# SOCPSBanks.net
KiCad netlist of a schematic drawn in Altium Designer
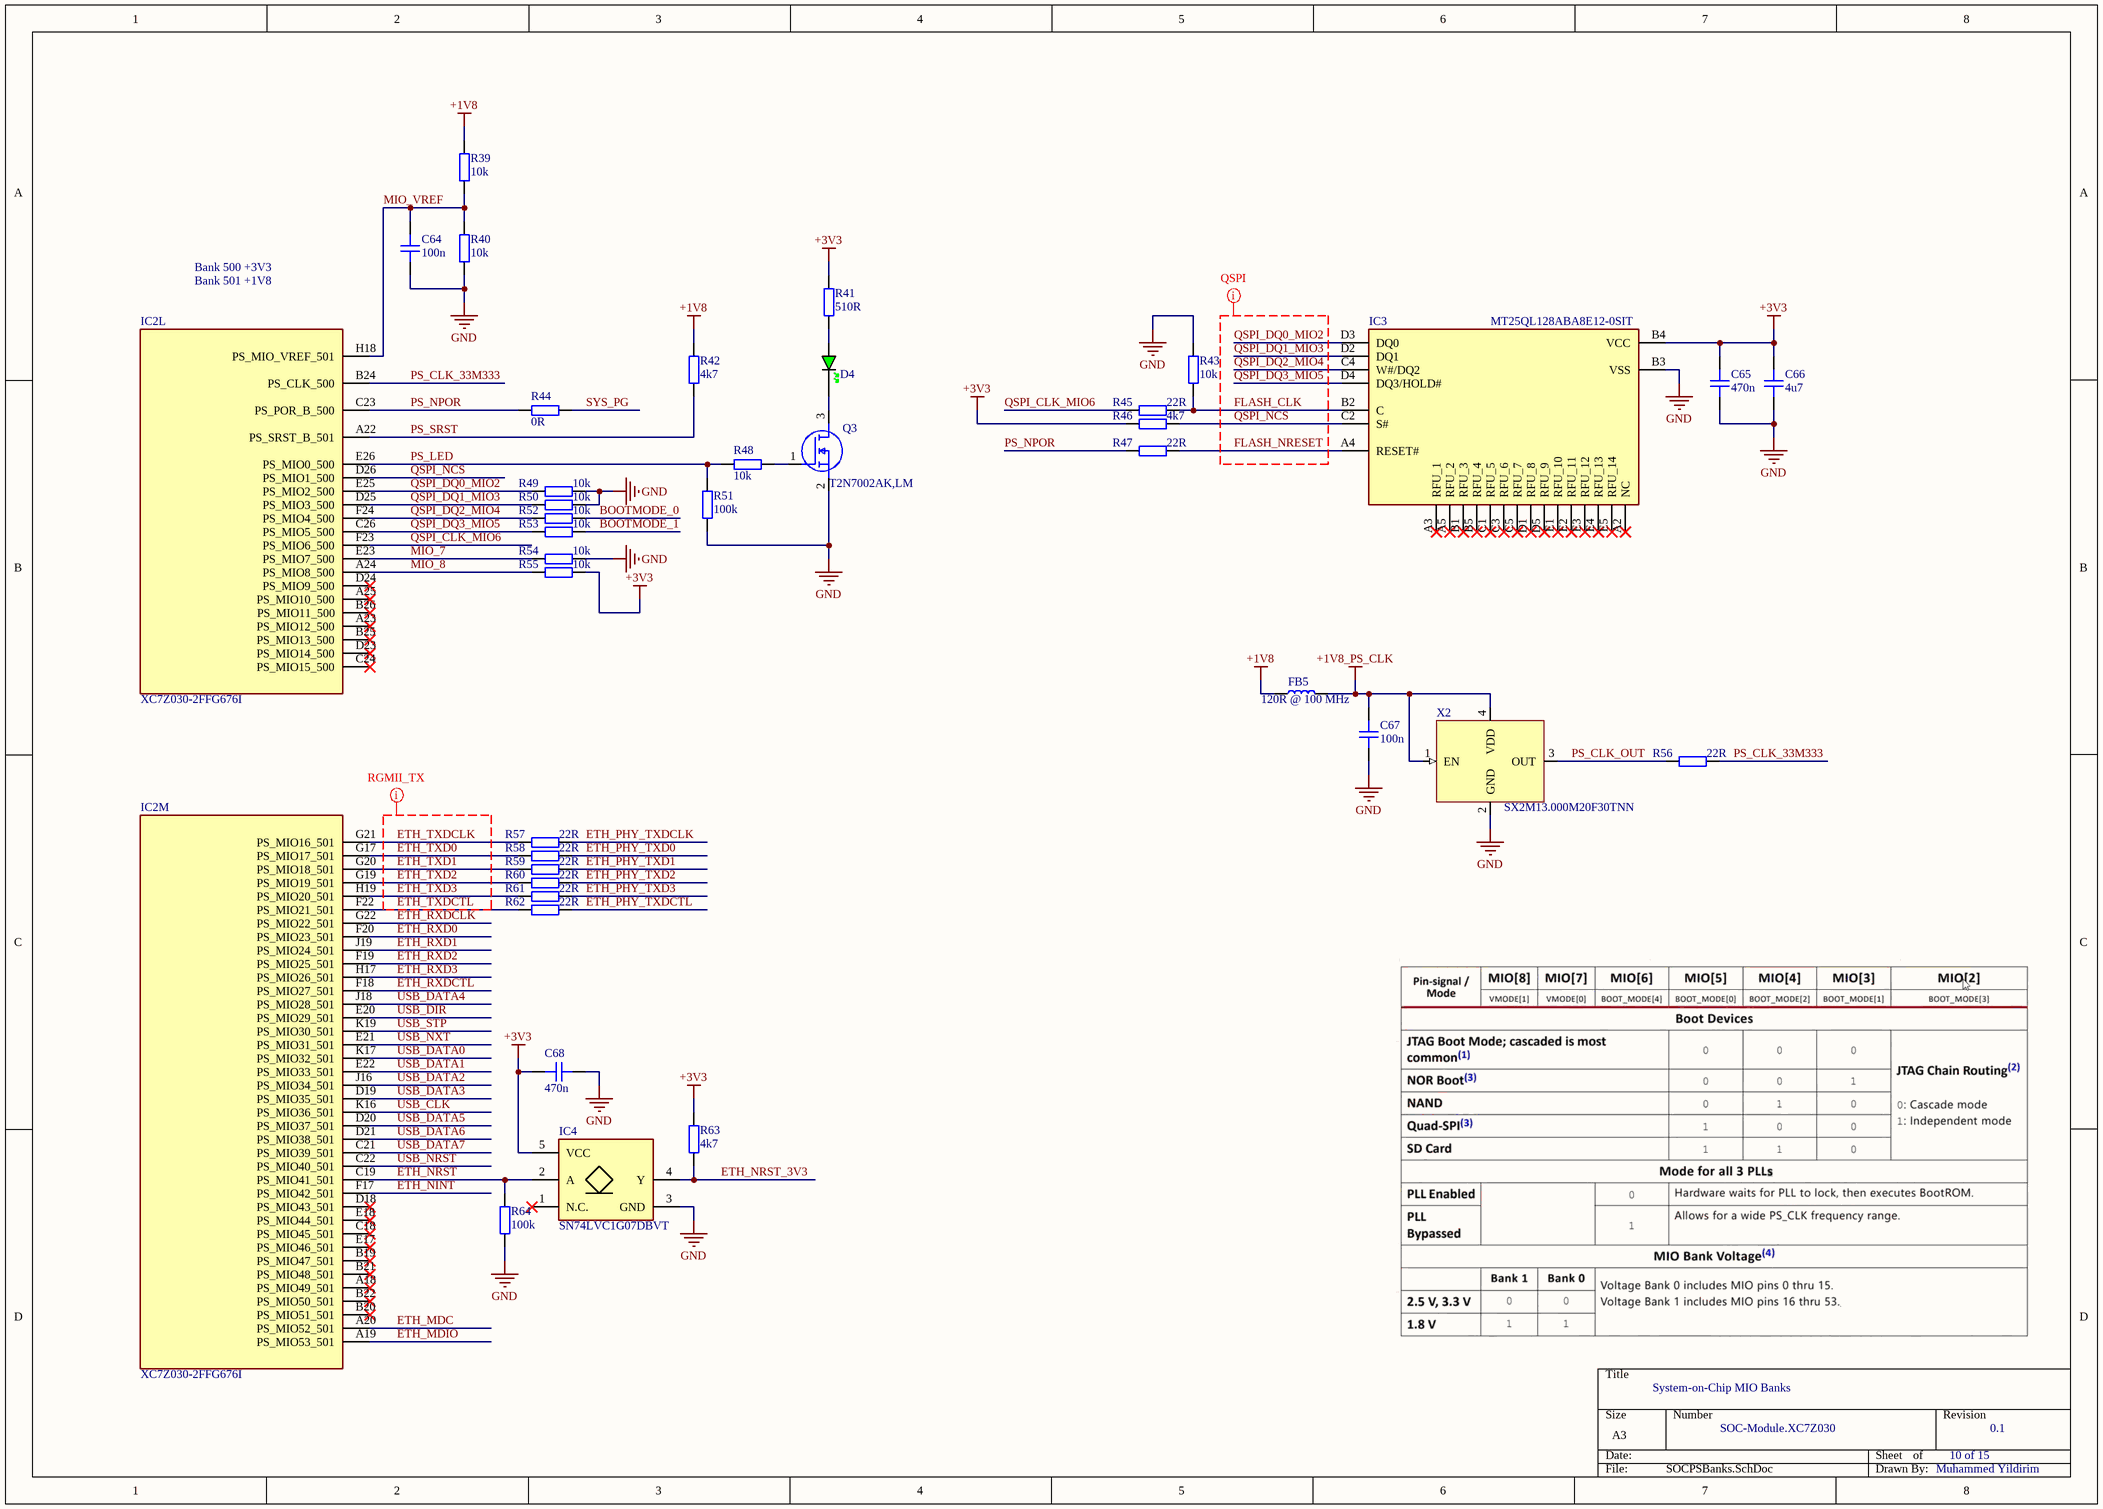
[diagram p0: SOCPSBanks.SchDoc]

(export (version "E")
  (design (tool "Eeschema 10.0.6"))
  (components
    (comp (ref "C64")
      (value "100n")
      (footprint "CAP_0201")
      (description "Capacitor SMD 0201")
      (libsource (lib "Schematic-Lib-PhilsLab") (part "CAP_0201"))
    )
    (comp (ref "C65")
      (value "470n")
      (footprint "CAP_0201")
      (description "Capacitor SMD 0201")
      (libsource (lib "Schematic-Lib-PhilsLab") (part "CAP_0201"))
    )
    (comp (ref "C66")
      (value "4u7")
      (footprint "CAP_0402")
      (description "Capacitor SMD 0402")
      (libsource (lib "Schematic-Lib-PhilsLab") (part "CAP_0402"))
    )
    (comp (ref "C67")
      (value "100n")
      (footprint "CAP_0201")
      (description "Capacitor SMD 0201")
      (libsource (lib "Schematic-Lib-PhilsLab") (part "CAP_0201"))
    )
    (comp (ref "C68")
      (value "470n")
      (footprint "CAP_0201")
      (description "Capacitor SMD 0201")
      (libsource (lib "Schematic-Lib-PhilsLab") (part "CAP_0201"))
    )
    (comp (ref "D4")
      (value "GREEN")
      (footprint "LED_0603_GREEN")
      (description "LED 0603 GREEN SMD")
      (libsource (lib "Schematic-Lib-PhilsLab") (part "LED_0603_GREEN"))
    )
    (comp (ref "FB5")
      (value "120R @ 100 MHz")
      (footprint "Footprint-Lib-PhilsLab:IND_0201")
      (description "Inductor SMD 0201")
      (fields
        (field (name "MANUFACTURER_PART_NUMBER") "LQP03HQ56NH02D")
        (field (name "MOUSER PART NUMBER") "81-LQP03HQ56NH02D")
      )
      (libsource (lib "Schematic-Lib-PhilsLab") (part "IND_0201"))
    )
    (comp (ref "IC2")
      (value "XC7Z030-2FFG676I")
      (footprint "XC7Z030PCBLib:BGA676C100P26X26_2700X2700X324")
      (description "Integrated Circuit")
      (fields (field (name "MOUSER PART NUMBER") "217-XC7Z030-2FFG676I"))
      (libsource (lib "XC7Z030SCHLib") (part "XC7Z030-2FFG676I"))
    )
    (comp (ref "IC3")
      (value "MT25QL128ABA8E12-0SIT")
      (footprint "XC7Z030PCBLib:BGA24C100P5X5_600X800X120")
      (description "Micron 128 Mb QSPI NOR-Flash")
      (fields (field (name "MOUSER PART NUMBER") "340-283174-TRAY"))
      (libsource (lib "XC7Z030SCHLib") (part "MT25QL128ABA8E12-0SIT"))
    )
    (comp (ref "IC4")
      (value "SN74LVC1G07DBVT")
      (footprint "XC7Z030PCBLib:SOT95P280X145-5N")
      (description "Integrated Circuit")
      (fields (field (name "MOUSER PART NUMBER") "595-SN74LVC1G07DBVT"))
      (libsource (lib "XC7Z030SCHLib") (part "SN74LVC1G07DBVT"))
    )
    (comp (ref "Q3")
      (value "T2N7002AK,LM")
      (footprint "Footprint-Lib-PhilsLab:TBAT54CLM")
      (description "MOSFET (N-Channel)")
      (fields (field (name "MOUSER PART NUMBER") "757-T2N7002AKLM"))
      (libsource (lib "Schematic-Lib-PhilsLab") (part "T2N7002AK,LM"))
    )
    (comp (ref "R39")
      (value "10k")
      (footprint "RES_0201")
      (description "Resistor SMD 0201")
      (libsource (lib "Schematic-Lib-PhilsLab") (part "RES_0201"))
    )
    (comp (ref "R40")
      (value "10k")
      (footprint "RES_0201")
      (description "Resistor SMD 0201")
      (libsource (lib "Schematic-Lib-PhilsLab") (part "RES_0201"))
    )
    (comp (ref "R41")
      (value "510R")
      (footprint "RES_0603")
      (description "Resistor SMD 0603")
      (libsource (lib "Schematic-Lib-PhilsLab") (part "RES_0603"))
    )
    (comp (ref "R42")
      (value "4k7")
      (footprint "RES_0201")
      (description "Resistor SMD 0201")
      (libsource (lib "Schematic-Lib-PhilsLab") (part "RES_0201"))
    )
    (comp (ref "R43")
      (value "10k")
      (footprint "RES_0201")
      (description "Resistor SMD 0201")
      (libsource (lib "Schematic-Lib-PhilsLab") (part "RES_0201"))
    )
    (comp (ref "R44")
      (value "0R")
      (footprint "RES_0402")
      (description "Resistor SMD 0402")
      (libsource (lib "Schematic-Lib-PhilsLab") (part "RES_0402"))
    )
    (comp (ref "R45")
      (value "22R")
      (footprint "RES_0201")
      (description "Resistor SMD 0201")
      (libsource (lib "Schematic-Lib-PhilsLab") (part "RES_0201"))
    )
    (comp (ref "R46")
      (value "4k7")
      (footprint "RES_0201")
      (description "Resistor SMD 0201")
      (libsource (lib "Schematic-Lib-PhilsLab") (part "RES_0201"))
    )
    (comp (ref "R47")
      (value "22R")
      (footprint "RES_0201")
      (description "Resistor SMD 0201")
      (libsource (lib "Schematic-Lib-PhilsLab") (part "RES_0201"))
    )
    (comp (ref "R48")
      (value "10k")
      (footprint "RES_0201")
      (description "Resistor SMD 0201")
      (libsource (lib "Schematic-Lib-PhilsLab") (part "RES_0201"))
    )
    (comp (ref "R49")
      (value "10k")
      (footprint "RES_0201")
      (description "Resistor SMD 0201")
      (libsource (lib "Schematic-Lib-PhilsLab") (part "RES_0201"))
    )
    (comp (ref "R50")
      (value "10k")
      (footprint "RES_0201")
      (description "Resistor SMD 0201")
      (libsource (lib "Schematic-Lib-PhilsLab") (part "RES_0201"))
    )
    (comp (ref "R51")
      (value "100k")
      (footprint "RES_0201")
      (description "Resistor SMD 0201")
      (libsource (lib "Schematic-Lib-PhilsLab") (part "RES_0201"))
    )
    (comp (ref "R52")
      (value "10k")
      (footprint "RES_0201")
      (description "Resistor SMD 0201")
      (libsource (lib "Schematic-Lib-PhilsLab") (part "RES_0201"))
    )
    (comp (ref "R53")
      (value "10k")
      (footprint "RES_0201")
      (description "Resistor SMD 0201")
      (libsource (lib "Schematic-Lib-PhilsLab") (part "RES_0201"))
    )
    (comp (ref "R54")
      (value "10k")
      (footprint "RES_0201")
      (description "Resistor SMD 0201")
      (libsource (lib "Schematic-Lib-PhilsLab") (part "RES_0201"))
    )
    (comp (ref "R55")
      (value "10k")
      (footprint "RES_0201")
      (description "Resistor SMD 0201")
      (libsource (lib "Schematic-Lib-PhilsLab") (part "RES_0201"))
    )
    (comp (ref "R56")
      (value "22R")
      (footprint "RES_0201")
      (description "Resistor SMD 0201")
      (libsource (lib "Schematic-Lib-PhilsLab") (part "RES_0201"))
    )
    (comp (ref "R57")
      (value "22R")
      (footprint "RES_0201")
      (description "Resistor SMD 0201")
      (libsource (lib "Schematic-Lib-PhilsLab") (part "RES_0201"))
    )
    (comp (ref "R58")
      (value "22R")
      (footprint "RES_0201")
      (description "Resistor SMD 0201")
      (libsource (lib "Schematic-Lib-PhilsLab") (part "RES_0201"))
    )
    (comp (ref "R59")
      (value "22R")
      (footprint "RES_0201")
      (description "Resistor SMD 0201")
      (libsource (lib "Schematic-Lib-PhilsLab") (part "RES_0201"))
    )
    (comp (ref "R60")
      (value "22R")
      (footprint "RES_0201")
      (description "Resistor SMD 0201")
      (libsource (lib "Schematic-Lib-PhilsLab") (part "RES_0201"))
    )
    (comp (ref "R61")
      (value "22R")
      (footprint "RES_0201")
      (description "Resistor SMD 0201")
      (libsource (lib "Schematic-Lib-PhilsLab") (part "RES_0201"))
    )
    (comp (ref "R62")
      (value "22R")
      (footprint "RES_0201")
      (description "Resistor SMD 0201")
      (libsource (lib "Schematic-Lib-PhilsLab") (part "RES_0201"))
    )
    (comp (ref "R63")
      (value "4k7")
      (footprint "RES_0201")
      (description "Resistor SMD 0201")
      (libsource (lib "Schematic-Lib-PhilsLab") (part "RES_0201"))
    )
    (comp (ref "R64")
      (value "100k")
      (footprint "RES_0201")
      (description "Resistor SMD 0201")
      (libsource (lib "Schematic-Lib-PhilsLab") (part "RES_0201"))
    )
    (comp (ref "X2")
      (value "SX2M13.000M20F30TNN")
      (footprint "XTAL_2520")
      (fields
        (field (name "MANUFACTURER") "ECS")
        (field (name "MANUFACTURER PART NUMBER") "ECS-2520MV-130-BN-TR")
      )
      (libsource (lib "Schematic-Lib-PhilsLab") (part "ECS-2520MV-130-BN-TR"))
    )
  )
  (nets
    (net (code "1") (name "+1V8") (class "Default")
      (node (ref "FB5") (pin "1") (pinfunction "1_1") (pintype "passive"))
      (node (ref "R39") (pin "1") (pinfunction "1_1") (pintype "passive"))
      (node (ref "R42") (pin "2") (pinfunction "2_2") (pintype "passive"))
    )
    (net (code "2") (name "+1V8_PS_CLK") (class "Default")
      (node (ref "C67") (pin "1") (pinfunction "1_1") (pintype "passive"))
      (node (ref "FB5") (pin "2") (pinfunction "2_2") (pintype "passive"))
      (node (ref "X2") (pin "1") (pinfunction "EN_1") (pintype "input"))
      (node (ref "X2") (pin "4") (pinfunction "VDD_4") (pintype "power_in"))
    )
    (net (code "3") (name "+3V3") (class "Default")
      (node (ref "C65") (pin "2") (pinfunction "2_2") (pintype "passive"))
      (node (ref "C66") (pin "2") (pinfunction "2_2") (pintype "passive"))
      (node (ref "C68") (pin "2") (pinfunction "2_2") (pintype "passive"))
      (node (ref "IC3") (pin "B4") (pinfunction "VCC_B4") (pintype "passive"))
      (node (ref "IC4") (pin "5") (pinfunction "VCC_5") (pintype "passive"))
      (node (ref "R41") (pin "2") (pinfunction "2_2") (pintype "passive"))
      (node (ref "R46") (pin "2") (pinfunction "2_2") (pintype "passive"))
      (node (ref "R55") (pin "1") (pinfunction "1_1") (pintype "passive"))
      (node (ref "R63") (pin "2") (pinfunction "2_2") (pintype "passive"))
    )
    (net (code "4") (name "/BOOTMODE_0") (class "Default")
      (node (ref "R52") (pin "1") (pinfunction "1_1") (pintype "passive"))
    )
    (net (code "5") (name "/BOOTMODE_1") (class "Default")
      (node (ref "R53") (pin "1") (pinfunction "1_1") (pintype "passive"))
    )
    (net (code "6") (name "/ETH_MDC") (class "Default")
      (node (ref "IC2") (pin "A20") (pinfunction "PS_MIO52_501_A20") (pintype "passive"))
    )
    (net (code "7") (name "/ETH_MDIO") (class "Default")
      (node (ref "IC2") (pin "A19") (pinfunction "PS_MIO53_501_A19") (pintype "passive"))
    )
    (net (code "8") (name "/ETH_NINT") (class "Default")
      (node (ref "IC2") (pin "F17") (pinfunction "PS_MIO42_501_F17") (pintype "passive"))
    )
    (net (code "9") (name "/ETH_NRST") (class "Default")
      (node (ref "IC2") (pin "C19") (pinfunction "PS_MIO41_501_C19") (pintype "passive"))
      (node (ref "IC4") (pin "2") (pinfunction "A_2") (pintype "passive"))
      (node (ref "R64") (pin "2") (pinfunction "2_2") (pintype "passive"))
    )
    (net (code "10") (name "/ETH_NRST_3V3") (class "Default")
      (node (ref "IC4") (pin "4") (pinfunction "Y_4") (pintype "passive"))
      (node (ref "R63") (pin "1") (pinfunction "1_1") (pintype "passive"))
    )
    (net (code "11") (name "/ETH_PHY_TXD0") (class "Default")
      (node (ref "R58") (pin "1") (pinfunction "1_1") (pintype "passive"))
    )
    (net (code "12") (name "/ETH_PHY_TXD1") (class "Default")
      (node (ref "R59") (pin "1") (pinfunction "1_1") (pintype "passive"))
    )
    (net (code "13") (name "/ETH_PHY_TXD2") (class "Default")
      (node (ref "R60") (pin "1") (pinfunction "1_1") (pintype "passive"))
    )
    (net (code "14") (name "/ETH_PHY_TXD3") (class "Default")
      (node (ref "R61") (pin "1") (pinfunction "1_1") (pintype "passive"))
    )
    (net (code "15") (name "/ETH_PHY_TXDCLK") (class "Default")
      (node (ref "R57") (pin "1") (pinfunction "1_1") (pintype "passive"))
    )
    (net (code "16") (name "/ETH_PHY_TXDCTL") (class "Default")
      (node (ref "R62") (pin "1") (pinfunction "1_1") (pintype "passive"))
    )
    (net (code "17") (name "/ETH_RXD0") (class "Default")
      (node (ref "IC2") (pin "F20") (pinfunction "PS_MIO23_501_F20") (pintype "passive"))
    )
    (net (code "18") (name "/ETH_RXD1") (class "Default")
      (node (ref "IC2") (pin "J19") (pinfunction "PS_MIO24_501_J19") (pintype "passive"))
    )
    (net (code "19") (name "/ETH_RXD2") (class "Default")
      (node (ref "IC2") (pin "F19") (pinfunction "PS_MIO25_501_F19") (pintype "passive"))
    )
    (net (code "20") (name "/ETH_RXD3") (class "Default")
      (node (ref "IC2") (pin "H17") (pinfunction "PS_MIO26_501_H17") (pintype "passive"))
    )
    (net (code "21") (name "/ETH_RXDCLK") (class "Default")
      (node (ref "IC2") (pin "G22") (pinfunction "PS_MIO22_501_G22") (pintype "passive"))
    )
    (net (code "22") (name "/ETH_RXDCTL") (class "Default")
      (node (ref "IC2") (pin "F18") (pinfunction "PS_MIO27_501_F18") (pintype "passive"))
    )
    (net (code "23") (name "/ETH_TXD0") (class "Default")
      (node (ref "IC2") (pin "G17") (pinfunction "PS_MIO17_501_G17") (pintype "passive"))
      (node (ref "R58") (pin "2") (pinfunction "2_2") (pintype "passive"))
    )
    (net (code "24") (name "/ETH_TXD1") (class "Default")
      (node (ref "IC2") (pin "G20") (pinfunction "PS_MIO18_501_G20") (pintype "passive"))
      (node (ref "R59") (pin "2") (pinfunction "2_2") (pintype "passive"))
    )
    (net (code "25") (name "/ETH_TXD2") (class "Default")
      (node (ref "IC2") (pin "G19") (pinfunction "PS_MIO19_501_G19") (pintype "passive"))
      (node (ref "R60") (pin "2") (pinfunction "2_2") (pintype "passive"))
    )
    (net (code "26") (name "/ETH_TXD3") (class "Default")
      (node (ref "IC2") (pin "H19") (pinfunction "PS_MIO20_501_H19") (pintype "passive"))
      (node (ref "R61") (pin "2") (pinfunction "2_2") (pintype "passive"))
    )
    (net (code "27") (name "/ETH_TXDCLK") (class "Default")
      (node (ref "IC2") (pin "G21") (pinfunction "PS_MIO16_501_G21") (pintype "passive"))
      (node (ref "R57") (pin "2") (pinfunction "2_2") (pintype "passive"))
    )
    (net (code "28") (name "/ETH_TXDCTL") (class "Default")
      (node (ref "IC2") (pin "F22") (pinfunction "PS_MIO21_501_F22") (pintype "passive"))
      (node (ref "R62") (pin "2") (pinfunction "2_2") (pintype "passive"))
    )
    (net (code "29") (name "/FLASH_CLK") (class "Default")
      (node (ref "IC3") (pin "B2") (pinfunction "C_B2") (pintype "passive"))
      (node (ref "R43") (pin "2") (pinfunction "2_2") (pintype "passive"))
      (node (ref "R45") (pin "1") (pinfunction "1_1") (pintype "passive"))
    )
    (net (code "30") (name "/FLASH_NRESET") (class "Default")
      (node (ref "IC3") (pin "A4") (pinfunction "RESET#_A4") (pintype "passive"))
      (node (ref "R47") (pin "1") (pinfunction "1_1") (pintype "passive"))
    )
    (net (code "31") (name "/MIO_7") (class "Default")
      (node (ref "IC2") (pin "E23") (pinfunction "PS_MIO7_500_E23") (pintype "passive"))
      (node (ref "R54") (pin "2") (pinfunction "2_2") (pintype "passive"))
    )
    (net (code "32") (name "/MIO_8") (class "Default")
      (node (ref "IC2") (pin "A24") (pinfunction "PS_MIO8_500_A24") (pintype "passive"))
      (node (ref "R55") (pin "2") (pinfunction "2_2") (pintype "passive"))
    )
    (net (code "33") (name "/MIO_VREF") (class "Default")
      (node (ref "C64") (pin "1") (pinfunction "1_1") (pintype "passive"))
      (node (ref "IC2") (pin "H18") (pinfunction "PS_MIO_VREF_501_H18") (pintype "passive"))
      (node (ref "R39") (pin "2") (pinfunction "2_2") (pintype "passive"))
      (node (ref "R40") (pin "1") (pinfunction "1_1") (pintype "passive"))
    )
    (net (code "34") (name "/PS_CLK_33M333") (class "Default")
      (node (ref "IC2") (pin "B24") (pinfunction "PS_CLK_500_B24") (pintype "passive"))
      (node (ref "R56") (pin "2") (pinfunction "2_2") (pintype "passive"))
    )
    (net (code "35") (name "/PS_CLK_OUT") (class "Default")
      (node (ref "R56") (pin "1") (pinfunction "1_1") (pintype "passive"))
      (node (ref "X2") (pin "3") (pinfunction "OUT_3") (pintype "passive"))
    )
    (net (code "36") (name "/PS_LED") (class "Default")
      (node (ref "IC2") (pin "E26") (pinfunction "PS_MIO0_500_E26") (pintype "passive"))
      (node (ref "R48") (pin "2") (pinfunction "2_2") (pintype "passive"))
      (node (ref "R51") (pin "2") (pinfunction "2_2") (pintype "passive"))
    )
    (net (code "37") (name "/PS_NPOR") (class "Default")
      (node (ref "IC2") (pin "C23") (pinfunction "PS_POR_B_500_C23") (pintype "passive"))
      (node (ref "R44") (pin "2") (pinfunction "2_2") (pintype "passive"))
      (node (ref "R47") (pin "2") (pinfunction "2_2") (pintype "passive"))
    )
    (net (code "38") (name "/PS_SRST") (class "Default")
      (node (ref "IC2") (pin "A22") (pinfunction "PS_SRST_B_501_A22") (pintype "passive"))
      (node (ref "R42") (pin "1") (pinfunction "1_1") (pintype "passive"))
    )
    (net (code "39") (name "/QSPI_CLK_MIO6") (class "Default")
      (node (ref "IC2") (pin "F23") (pinfunction "PS_MIO6_500_F23") (pintype "passive"))
      (node (ref "R45") (pin "2") (pinfunction "2_2") (pintype "passive"))
    )
    (net (code "40") (name "/QSPI_DQ0_MIO2") (class "Default")
      (node (ref "IC2") (pin "E25") (pinfunction "PS_MIO2_500_E25") (pintype "passive"))
      (node (ref "IC3") (pin "D3") (pinfunction "DQ0_D3") (pintype "passive"))
      (node (ref "R49") (pin "2") (pinfunction "2_2") (pintype "passive"))
    )
    (net (code "41") (name "/QSPI_DQ1_MIO3") (class "Default")
      (node (ref "IC2") (pin "D25") (pinfunction "PS_MIO3_500_D25") (pintype "passive"))
      (node (ref "IC3") (pin "D2") (pinfunction "DQ1_D2") (pintype "passive"))
      (node (ref "R50") (pin "2") (pinfunction "2_2") (pintype "passive"))
    )
    (net (code "42") (name "/QSPI_DQ2_MIO4") (class "Default")
      (node (ref "IC2") (pin "F24") (pinfunction "PS_MIO4_500_F24") (pintype "passive"))
      (node (ref "IC3") (pin "C4") (pinfunction "W#/DQ2_C4") (pintype "passive"))
      (node (ref "R52") (pin "2") (pinfunction "2_2") (pintype "passive"))
    )
    (net (code "43") (name "/QSPI_DQ3_MIO5") (class "Default")
      (node (ref "IC2") (pin "C26") (pinfunction "PS_MIO5_500_C26") (pintype "passive"))
      (node (ref "IC3") (pin "D4") (pinfunction "DQ3/HOLD#_D4") (pintype "passive"))
      (node (ref "R53") (pin "2") (pinfunction "2_2") (pintype "passive"))
    )
    (net (code "44") (name "/QSPI_NCS") (class "Default")
      (node (ref "IC2") (pin "D26") (pinfunction "PS_MIO1_500_D26") (pintype "passive"))
      (node (ref "IC3") (pin "C2") (pinfunction "S#_C2") (pintype "passive"))
      (node (ref "R46") (pin "1") (pinfunction "1_1") (pintype "passive"))
    )
    (net (code "45") (name "/SYS_PG") (class "Default")
      (node (ref "R44") (pin "1") (pinfunction "1_1") (pintype "passive"))
    )
    (net (code "46") (name "/USB_CLK") (class "Default")
      (node (ref "IC2") (pin "K16") (pinfunction "PS_MIO36_501_K16") (pintype "passive"))
    )
    (net (code "47") (name "/USB_DATA0") (class "Default")
      (node (ref "IC2") (pin "K17") (pinfunction "PS_MIO32_501_K17") (pintype "passive"))
    )
    (net (code "48") (name "/USB_DATA1") (class "Default")
      (node (ref "IC2") (pin "E22") (pinfunction "PS_MIO33_501_E22") (pintype "passive"))
    )
    (net (code "49") (name "/USB_DATA2") (class "Default")
      (node (ref "IC2") (pin "J16") (pinfunction "PS_MIO34_501_J16") (pintype "passive"))
    )
    (net (code "50") (name "/USB_DATA3") (class "Default")
      (node (ref "IC2") (pin "D19") (pinfunction "PS_MIO35_501_D19") (pintype "passive"))
    )
    (net (code "51") (name "/USB_DATA4") (class "Default")
      (node (ref "IC2") (pin "J18") (pinfunction "PS_MIO28_501_J18") (pintype "passive"))
    )
    (net (code "52") (name "/USB_DATA5") (class "Default")
      (node (ref "IC2") (pin "D20") (pinfunction "PS_MIO37_501_D20") (pintype "passive"))
    )
    (net (code "53") (name "/USB_DATA6") (class "Default")
      (node (ref "IC2") (pin "D21") (pinfunction "PS_MIO38_501_D21") (pintype "passive"))
    )
    (net (code "54") (name "/USB_DATA7") (class "Default")
      (node (ref "IC2") (pin "C21") (pinfunction "PS_MIO39_501_C21") (pintype "passive"))
    )
    (net (code "55") (name "/USB_DIR") (class "Default")
      (node (ref "IC2") (pin "E20") (pinfunction "PS_MIO29_501_E20") (pintype "passive"))
    )
    (net (code "56") (name "/USB_NRST") (class "Default")
      (node (ref "IC2") (pin "C22") (pinfunction "PS_MIO40_501_C22") (pintype "passive"))
    )
    (net (code "57") (name "/USB_NXT") (class "Default")
      (node (ref "IC2") (pin "E21") (pinfunction "PS_MIO31_501_E21") (pintype "passive"))
    )
    (net (code "58") (name "/USB_STP") (class "Default")
      (node (ref "IC2") (pin "K19") (pinfunction "PS_MIO30_501_K19") (pintype "passive"))
    )
    (net (code "59") (name "GND") (class "Default")
      (node (ref "C64") (pin "2") (pinfunction "2_2") (pintype "passive"))
      (node (ref "C65") (pin "1") (pinfunction "1_1") (pintype "passive"))
      (node (ref "C66") (pin "1") (pinfunction "1_1") (pintype "passive"))
      (node (ref "C67") (pin "2") (pinfunction "2_2") (pintype "passive"))
      (node (ref "C68") (pin "1") (pinfunction "1_1") (pintype "passive"))
      (node (ref "IC3") (pin "B3") (pinfunction "VSS_B3") (pintype "passive"))
      (node (ref "IC4") (pin "3") (pinfunction "GND_3") (pintype "passive"))
      (node (ref "Q3") (pin "2") (pinfunction "S_2") (pintype "passive"))
      (node (ref "R40") (pin "2") (pinfunction "2_2") (pintype "passive"))
      (node (ref "R43") (pin "1") (pinfunction "1_1") (pintype "passive"))
      (node (ref "R49") (pin "1") (pinfunction "1_1") (pintype "passive"))
      (node (ref "R50") (pin "1") (pinfunction "1_1") (pintype "passive"))
      (node (ref "R51") (pin "1") (pinfunction "1_1") (pintype "passive"))
      (node (ref "R54") (pin "1") (pinfunction "1_1") (pintype "passive"))
      (node (ref "R64") (pin "1") (pinfunction "1_1") (pintype "passive"))
      (node (ref "X2") (pin "2") (pinfunction "GND_2") (pintype "power_in"))
    )
    (net (code "60") (name "Net-(D4-PadA)") (class "Default")
      (node (ref "D4") (pin "A") (pinfunction "A_A") (pintype "passive"))
      (node (ref "R41") (pin "1") (pinfunction "1_1") (pintype "passive"))
    )
    (net (code "61") (name "Net-(Q3-D)") (class "Default")
      (node (ref "D4") (pin "K") (pinfunction "K_K") (pintype "passive"))
      (node (ref "Q3") (pin "3") (pinfunction "D_3") (pintype "passive"))
    )
    (net (code "62") (name "Net-(Q3-G)") (class "Default")
      (node (ref "Q3") (pin "1") (pinfunction "G_1") (pintype "passive"))
      (node (ref "R48") (pin "1") (pinfunction "1_1") (pintype "passive"))
    )
    (net (code "63") (name "unconnected-(IC2L-PS_MIO9_500-PadD24)") (class "Default")
      (node (ref "IC2") (pin "D24") (pinfunction "PS_MIO9_500_D24") (pintype "passive+no_connect"))
    )
    (net (code "64") (name "unconnected-(IC2L-PS_MIO10_500-PadA25)") (class "Default")
      (node (ref "IC2") (pin "A25") (pinfunction "PS_MIO10_500_A25") (pintype "passive+no_connect"))
    )
    (net (code "65") (name "unconnected-(IC2L-PS_MIO11_500-PadB26)") (class "Default")
      (node (ref "IC2") (pin "B26") (pinfunction "PS_MIO11_500_B26") (pintype "passive+no_connect"))
    )
    (net (code "66") (name "unconnected-(IC2L-PS_MIO12_500-PadA23)") (class "Default")
      (node (ref "IC2") (pin "A23") (pinfunction "PS_MIO12_500_A23") (pintype "passive+no_connect"))
    )
    (net (code "67") (name "unconnected-(IC2L-PS_MIO13_500-PadB25)") (class "Default")
      (node (ref "IC2") (pin "B25") (pinfunction "PS_MIO13_500_B25") (pintype "passive+no_connect"))
    )
    (net (code "68") (name "unconnected-(IC2L-PS_MIO14_500-PadD23)") (class "Default")
      (node (ref "IC2") (pin "D23") (pinfunction "PS_MIO14_500_D23") (pintype "passive+no_connect"))
    )
    (net (code "69") (name "unconnected-(IC2L-PS_MIO15_500-PadC24)") (class "Default")
      (node (ref "IC2") (pin "C24") (pinfunction "PS_MIO15_500_C24") (pintype "passive+no_connect"))
    )
    (net (code "70") (name "unconnected-(IC2M-PS_MIO43_501-PadD18)") (class "Default")
      (node (ref "IC2") (pin "D18") (pinfunction "PS_MIO43_501_D18") (pintype "passive+no_connect"))
    )
    (net (code "71") (name "unconnected-(IC2M-PS_MIO44_501-PadE18)") (class "Default")
      (node (ref "IC2") (pin "E18") (pinfunction "PS_MIO44_501_E18") (pintype "passive+no_connect"))
    )
    (net (code "72") (name "unconnected-(IC2M-PS_MIO45_501-PadC18)") (class "Default")
      (node (ref "IC2") (pin "C18") (pinfunction "PS_MIO45_501_C18") (pintype "passive+no_connect"))
    )
    (net (code "73") (name "unconnected-(IC2M-PS_MIO46_501-PadE17)") (class "Default")
      (node (ref "IC2") (pin "E17") (pinfunction "PS_MIO46_501_E17") (pintype "passive+no_connect"))
    )
    (net (code "74") (name "unconnected-(IC2M-PS_MIO47_501-PadB19)") (class "Default")
      (node (ref "IC2") (pin "B19") (pinfunction "PS_MIO47_501_B19") (pintype "passive+no_connect"))
    )
    (net (code "75") (name "unconnected-(IC2M-PS_MIO48_501-PadB21)") (class "Default")
      (node (ref "IC2") (pin "B21") (pinfunction "PS_MIO48_501_B21") (pintype "passive+no_connect"))
    )
    (net (code "76") (name "unconnected-(IC2M-PS_MIO49_501-PadA18)") (class "Default")
      (node (ref "IC2") (pin "A18") (pinfunction "PS_MIO49_501_A18") (pintype "passive+no_connect"))
    )
    (net (code "77") (name "unconnected-(IC2M-PS_MIO50_501-PadB22)") (class "Default")
      (node (ref "IC2") (pin "B22") (pinfunction "PS_MIO50_501_B22") (pintype "passive+no_connect"))
    )
    (net (code "78") (name "unconnected-(IC2M-PS_MIO51_501-PadB20)") (class "Default")
      (node (ref "IC2") (pin "B20") (pinfunction "PS_MIO51_501_B20") (pintype "passive+no_connect"))
    )
    (net (code "79") (name "unconnected-(IC3-NC-PadA2)") (class "Default")
      (node (ref "IC3") (pin "A2") (pinfunction "NC_A2") (pintype "passive+no_connect"))
    )
    (net (code "80") (name "unconnected-(IC3-RFU_1-PadA3)") (class "Default")
      (node (ref "IC3") (pin "A3") (pinfunction "RFU_1_A3") (pintype "passive+no_connect"))
    )
    (net (code "81") (name "unconnected-(IC3-RFU_2-PadA5)") (class "Default")
      (node (ref "IC3") (pin "A5") (pinfunction "RFU_2_A5") (pintype "passive+no_connect"))
    )
    (net (code "82") (name "unconnected-(IC3-RFU_3-PadB1)") (class "Default")
      (node (ref "IC3") (pin "B1") (pinfunction "RFU_3_B1") (pintype "passive+no_connect"))
    )
    (net (code "83") (name "unconnected-(IC3-RFU_4-PadB5)") (class "Default")
      (node (ref "IC3") (pin "B5") (pinfunction "RFU_4_B5") (pintype "passive+no_connect"))
    )
    (net (code "84") (name "unconnected-(IC3-RFU_5-PadC1)") (class "Default")
      (node (ref "IC3") (pin "C1") (pinfunction "RFU_5_C1") (pintype "passive+no_connect"))
    )
    (net (code "85") (name "unconnected-(IC3-RFU_6-PadC3)") (class "Default")
      (node (ref "IC3") (pin "C3") (pinfunction "RFU_6_C3") (pintype "passive+no_connect"))
    )
    (net (code "86") (name "unconnected-(IC3-RFU_7-PadC5)") (class "Default")
      (node (ref "IC3") (pin "C5") (pinfunction "RFU_7_C5") (pintype "passive+no_connect"))
    )
    (net (code "87") (name "unconnected-(IC3-RFU_8-PadD1)") (class "Default")
      (node (ref "IC3") (pin "D1") (pinfunction "RFU_8_D1") (pintype "passive+no_connect"))
    )
    (net (code "88") (name "unconnected-(IC3-RFU_9-PadD5)") (class "Default")
      (node (ref "IC3") (pin "D5") (pinfunction "RFU_9_D5") (pintype "passive+no_connect"))
    )
    (net (code "89") (name "unconnected-(IC3-RFU_10-PadE1)") (class "Default")
      (node (ref "IC3") (pin "E1") (pinfunction "RFU_10_E1") (pintype "passive+no_connect"))
    )
    (net (code "90") (name "unconnected-(IC3-RFU_11-PadE2)") (class "Default")
      (node (ref "IC3") (pin "E2") (pinfunction "RFU_11_E2") (pintype "passive+no_connect"))
    )
    (net (code "91") (name "unconnected-(IC3-RFU_12-PadE3)") (class "Default")
      (node (ref "IC3") (pin "E3") (pinfunction "RFU_12_E3") (pintype "passive+no_connect"))
    )
    (net (code "92") (name "unconnected-(IC3-RFU_13-PadE4)") (class "Default")
      (node (ref "IC3") (pin "E4") (pinfunction "RFU_13_E4") (pintype "passive+no_connect"))
    )
    (net (code "93") (name "unconnected-(IC3-RFU_14-PadE5)") (class "Default")
      (node (ref "IC3") (pin "E5") (pinfunction "RFU_14_E5") (pintype "passive+no_connect"))
    )
    (net (code "94") (name "unconnected-(IC4-N.C.-Pad1)") (class "Default")
      (node (ref "IC4") (pin "1") (pinfunction "N.C._1") (pintype "passive+no_connect"))
    )
  )
)
